# old_main_board.net
KiCad netlist of a schematic drawn in EAGLE
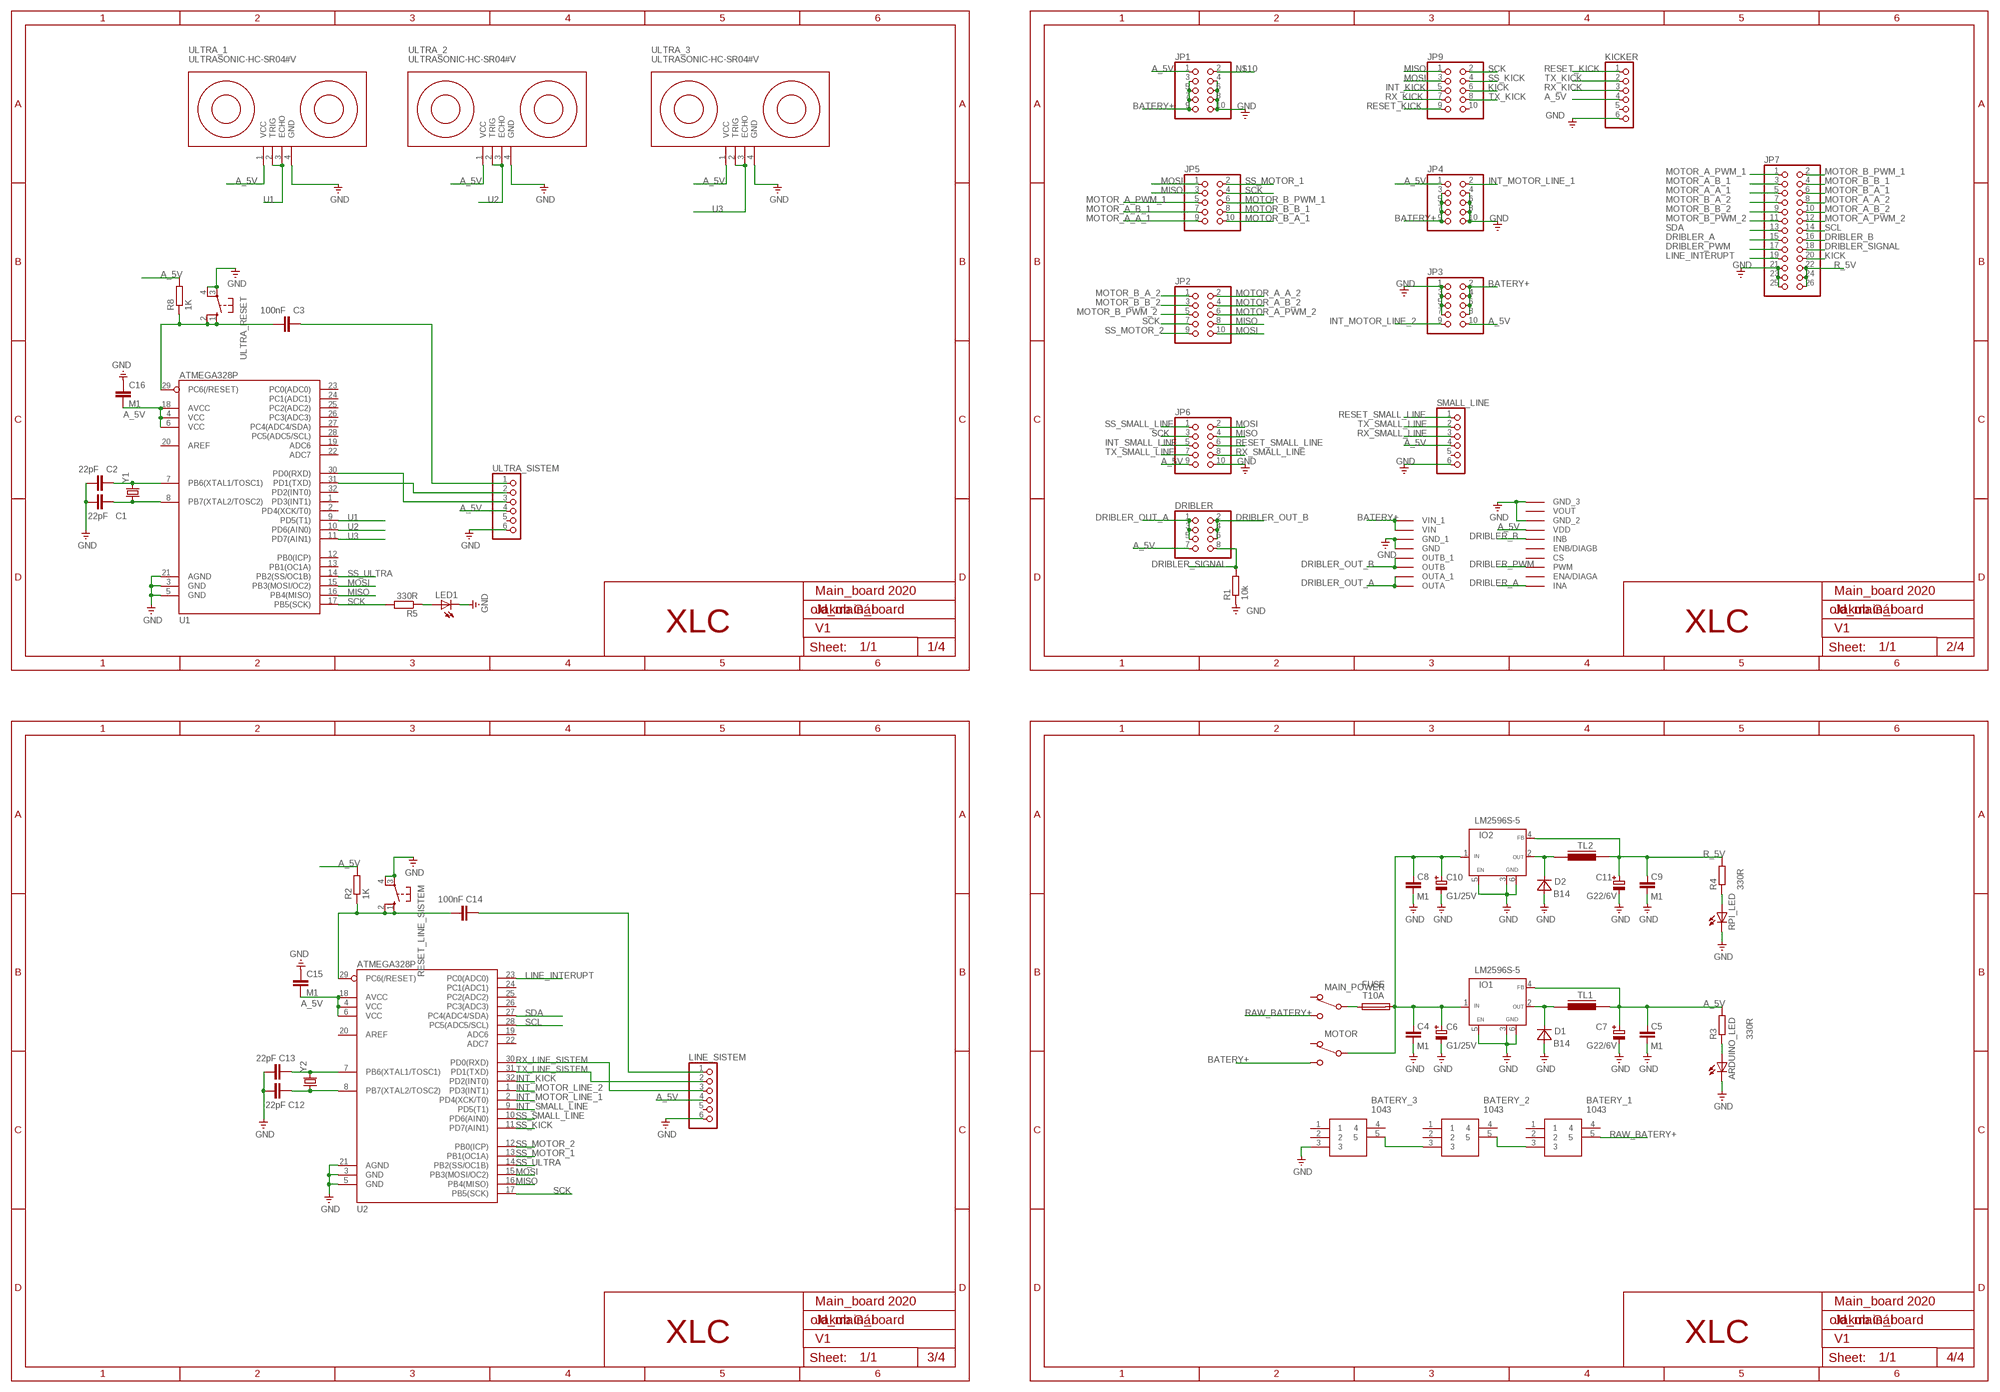
[diagram p0: schematic, sheet 1]

(export (version "E")
  (design (tool "Eeschema 10.0.6"))
  (components
    (comp (ref "ARDUINO_LED")
      (value "LEDCHIPLED_0603")
      (footprint "eagle-import:CHIPLED_0603")
      (libsource (lib "eagle-import") (part "LEDCHIPLED_0603"))
    )
    (comp (ref "BATERY_1")
      (value "1043")
      (footprint "eagle-import:1043")
      (fields (field (name "MOUSER_PART_NUMBER") "534-1043"))
      (libsource (lib "eagle-import") (part "1043"))
    )
    (comp (ref "BATERY_2")
      (value "1043")
      (footprint "eagle-import:1043")
      (fields (field (name "MOUSER_PART_NUMBER") "534-1043"))
      (libsource (lib "eagle-import") (part "1043"))
    )
    (comp (ref "BATERY_3")
      (value "1043")
      (footprint "eagle-import:1043")
      (fields (field (name "MOUSER_PART_NUMBER") "534-1043"))
      (libsource (lib "eagle-import") (part "1043"))
    )
    (comp (ref "C1")
      (value "22pF")
      (footprint "eagle-import:C0603")
      (libsource (lib "eagle-import") (part "rcl@1_C-EUC0603"))
    )
    (comp (ref "C2")
      (value "22pF")
      (footprint "eagle-import:C0603")
      (libsource (lib "eagle-import") (part "rcl@1_C-EUC0603"))
    )
    (comp (ref "C3")
      (value "100nF")
      (footprint "eagle-import:C0603")
      (libsource (lib "eagle-import") (part "rcl@1_C-EUC0603"))
    )
    (comp (ref "C4")
      (value "M1")
      (footprint "eagle-import:SMD-1206")
      (libsource (lib "eagle-import") (part "KOND-KERAM1206-SMD"))
    )
    (comp (ref "C5")
      (value "M1")
      (footprint "eagle-import:SMD-1206")
      (libsource (lib "eagle-import") (part "KOND-KERAM1206-SMD"))
    )
    (comp (ref "C6")
      (value "G1/25V")
      (footprint "eagle-import:SMD-ELE-D")
      (libsource (lib "eagle-import") (part "KOND-ELEKTD-SMD"))
    )
    (comp (ref "C7")
      (value "G22/6V")
      (footprint "eagle-import:SMD-ELE-D")
      (libsource (lib "eagle-import") (part "KOND-ELEKTD-SMD"))
    )
    (comp (ref "C8")
      (value "M1")
      (footprint "eagle-import:SMD-1206")
      (libsource (lib "eagle-import") (part "KOND-KERAM1206-SMD"))
    )
    (comp (ref "C9")
      (value "M1")
      (footprint "eagle-import:SMD-1206")
      (libsource (lib "eagle-import") (part "KOND-KERAM1206-SMD"))
    )
    (comp (ref "C10")
      (value "G1/25V")
      (footprint "eagle-import:SMD-ELE-D")
      (libsource (lib "eagle-import") (part "KOND-ELEKTD-SMD"))
    )
    (comp (ref "C11")
      (value "G22/6V")
      (footprint "eagle-import:SMD-ELE-D")
      (libsource (lib "eagle-import") (part "KOND-ELEKTD-SMD"))
    )
    (comp (ref "C12")
      (value "22pF")
      (footprint "eagle-import:C0603")
      (libsource (lib "eagle-import") (part "rcl@1_C-EUC0603"))
    )
    (comp (ref "C13")
      (value "22pF")
      (footprint "eagle-import:C0603")
      (libsource (lib "eagle-import") (part "rcl@1_C-EUC0603"))
    )
    (comp (ref "C14")
      (value "100nF")
      (footprint "eagle-import:C0603")
      (libsource (lib "eagle-import") (part "rcl@1_C-EUC0603"))
    )
    (comp (ref "C15")
      (value "M1")
      (footprint "eagle-import:C0603")
      (libsource (lib "eagle-import") (part "C-EUC0603"))
    )
    (comp (ref "C16")
      (value "M1")
      (footprint "eagle-import:C0603")
      (libsource (lib "eagle-import") (part "C-EUC0603"))
    )
    (comp (ref "D1")
      (value "B14")
      (footprint "eagle-import:D-3,6X5,5")
      (libsource (lib "eagle-import") (part "DIODASMD-3,6X5,5"))
    )
    (comp (ref "D2")
      (value "B14")
      (footprint "eagle-import:D-3,6X5,5")
      (libsource (lib "eagle-import") (part "DIODASMD-3,6X5,5"))
    )
    (comp (ref "DRIBLER")
      (value "PINHD-2X4_2.54-SMD")
      (footprint "eagle-import:2X04SMD")
      (libsource (lib "eagle-import") (part "PINHD-2X4_2.54-SMD"))
    )
    (comp (ref "FUSE")
      (value "T10A")
      (footprint "eagle-import:SH22,5A")
      (libsource (lib "eagle-import") (part "POISTKA2A"))
    )
    (comp (ref "IO1")
      (value "LM2596S-5")
      (footprint "eagle-import:TO263-5")
      (libsource (lib "eagle-import") (part "LM2596S"))
    )
    (comp (ref "IO2")
      (value "LM2596S-5")
      (footprint "eagle-import:TO263-5")
      (libsource (lib "eagle-import") (part "LM2596S"))
    )
    (comp (ref "JP1")
      (value "PINHD-2X5IDC")
      (footprint "eagle-import:2X05_IDC")
      (libsource (lib "eagle-import") (part "PINHD-2X5IDC"))
    )
    (comp (ref "JP2")
      (value "PINHD-2X5IDC")
      (footprint "eagle-import:2X05_IDC")
      (libsource (lib "eagle-import") (part "PINHD-2X5IDC"))
    )
    (comp (ref "JP3")
      (value "PINHD-2X5IDC")
      (footprint "eagle-import:2X05_IDC")
      (libsource (lib "eagle-import") (part "PINHD-2X5IDC"))
    )
    (comp (ref "JP4")
      (value "PINHD-2X5IDC")
      (footprint "eagle-import:2X05_IDC")
      (libsource (lib "eagle-import") (part "PINHD-2X5IDC"))
    )
    (comp (ref "JP5")
      (value "PINHD-2X5IDC")
      (footprint "eagle-import:2X05_IDC")
      (libsource (lib "eagle-import") (part "PINHD-2X5IDC"))
    )
    (comp (ref "JP6")
      (value "PINHD-2X5IDC")
      (footprint "eagle-import:2X05_IDC")
      (libsource (lib "eagle-import") (part "PINHD-2X5IDC"))
    )
    (comp (ref "JP7")
      (value "PINHD-2X13_2.54")
      (footprint "eagle-import:2X13")
      (libsource (lib "eagle-import") (part "PINHD-2X13_2.54"))
    )
    (comp (ref "JP9")
      (value "PINHD-2X5IDC")
      (footprint "eagle-import:2X05_IDC")
      (libsource (lib "eagle-import") (part "PINHD-2X5IDC"))
    )
    (comp (ref "KICKER")
      (value "PINHD-1X6")
      (footprint "eagle-import:1X06")
      (libsource (lib "eagle-import") (part "PINHD-1X6"))
    )
    (comp (ref "LED1")
      (value "LEDCHIPLED_0603")
      (footprint "eagle-import:CHIPLED_0603")
      (libsource (lib "eagle-import") (part "LEDCHIPLED_0603"))
    )
    (comp (ref "LINE_SISTEM")
      (value "PINHD-1X6")
      (footprint "eagle-import:1X06")
      (libsource (lib "eagle-import") (part "PINHD-1X6"))
    )
    (comp (ref "MAIN_POWER")
      (value "PREP-1PB")
      (footprint "eagle-import:P-B069B")
      (libsource (lib "eagle-import") (part "PREP-1PB"))
    )
    (comp (ref "MOTOR")
      (value "PREP-1PB")
      (footprint "eagle-import:P-B069B")
      (libsource (lib "eagle-import") (part "PREP-1PB"))
    )
    (comp (ref "R1")
      (value "10k")
      (footprint "eagle-import:R0603")
      (libsource (lib "eagle-import") (part "R-EU_R0603"))
    )
    (comp (ref "R2")
      (value "1K")
      (footprint "eagle-import:R0603")
      (libsource (lib "eagle-import") (part "R-EU_R0603"))
    )
    (comp (ref "R3")
      (value "330R")
      (footprint "eagle-import:R0603")
      (libsource (lib "eagle-import") (part "R-EU_R0603"))
    )
    (comp (ref "R4")
      (value "330R")
      (footprint "eagle-import:R0603")
      (libsource (lib "eagle-import") (part "R-EU_R0603"))
    )
    (comp (ref "R5")
      (value "330R")
      (footprint "eagle-import:R0603")
      (libsource (lib "eagle-import") (part "R-EU_R0603"))
    )
    (comp (ref "R8")
      (value "1K")
      (footprint "eagle-import:R0603")
      (libsource (lib "eagle-import") (part "R-EU_R0603"))
    )
    (comp (ref "RESET_LINE_SISTEM")
      (value "10-XX")
      (footprint "eagle-import:B3F-10XX")
      (fields (field (name "MPN") "B3F-1000"))
      (libsource (lib "eagle-import") (part "10-XX"))
    )
    (comp (ref "RPI_LED")
      (value "LEDCHIPLED_0603")
      (footprint "eagle-import:CHIPLED_0603")
      (libsource (lib "eagle-import") (part "LEDCHIPLED_0603"))
    )
    (comp (ref "SMALL_LINE")
      (value "PINHD-1X6")
      (footprint "eagle-import:1X06")
      (libsource (lib "eagle-import") (part "PINHD-1X6"))
    )
    (comp (ref "TL1")
      (value "INDUK-TLSMD1")
      (footprint "eagle-import:INDUK-TL")
      (libsource (lib "eagle-import") (part "INDUK-TLSMD1"))
    )
    (comp (ref "TL2")
      (value "INDUK-TLSMD1")
      (footprint "eagle-import:INDUK-TL")
      (libsource (lib "eagle-import") (part "INDUK-TLSMD1"))
    )
    (comp (ref "U$4")
      (value "MOTOR_DRIVER")
      (footprint "eagle-import:MOTOR_DRIVER")
      (libsource (lib "eagle-import") (part "MOTOR_DRIVER"))
    )
    (comp (ref "U1")
      (value "ATMEGA328P")
      (footprint "eagle-import:TQFP32-08")
      (libsource (lib "eagle-import") (part "ATMEGA328_SMT"))
    )
    (comp (ref "U2")
      (value "ATMEGA328P")
      (footprint "eagle-import:TQFP32-08")
      (libsource (lib "eagle-import") (part "ATMEGA328_SMT"))
    )
    (comp (ref "ULTRA_1")
      (value "ULTRASONIC-HC-SR04#V")
      (footprint "eagle-import:ULTRASONIC-HC-SR04#V")
      (libsource (lib "eagle-import") (part "ULTRASONIC-HC-SR04#V"))
    )
    (comp (ref "ULTRA_2")
      (value "ULTRASONIC-HC-SR04#V")
      (footprint "eagle-import:ULTRASONIC-HC-SR04#V")
      (libsource (lib "eagle-import") (part "ULTRASONIC-HC-SR04#V"))
    )
    (comp (ref "ULTRA_3")
      (value "ULTRASONIC-HC-SR04#V")
      (footprint "eagle-import:ULTRASONIC-HC-SR04#V")
      (libsource (lib "eagle-import") (part "ULTRASONIC-HC-SR04#V"))
    )
    (comp (ref "ULTRA_RESET")
      (value "10-XX")
      (footprint "eagle-import:B3F-10XX")
      (fields (field (name "MPN") "B3F-1000"))
      (libsource (lib "eagle-import") (part "10-XX"))
    )
    (comp (ref "ULTRA_SISTEM")
      (value "PINHD-1X6")
      (footprint "eagle-import:1X06")
      (libsource (lib "eagle-import") (part "PINHD-1X6"))
    )
    (comp (ref "Y1")
      (value "CRYSTALHC49US")
      (footprint "eagle-import:HC49US")
      (libsource (lib "eagle-import") (part "CRYSTALHC49US"))
    )
    (comp (ref "Y2")
      (value "CRYSTALHC49US")
      (footprint "eagle-import:HC49US")
      (libsource (lib "eagle-import") (part "CRYSTALHC49US"))
    )
  )
  (nets
    (net (code "1") (name "/A_5V") (class "Default")
      (node (ref "C15") (pin "2") (pinfunction "2_2") (pintype "passive"))
      (node (ref "C16") (pin "2") (pinfunction "2_2") (pintype "passive"))
      (node (ref "C5") (pin "2") (pinfunction "2_2") (pintype "passive"))
      (node (ref "C7") (pin "PLUS") (pinfunction "PLUS_PLUS") (pintype "passive"))
      (node (ref "DRIBLER") (pin "7") (pinfunction "7_7") (pintype "passive"))
      (node (ref "IO1") (pin "4") (pinfunction "FB_4") (pintype "input"))
      (node (ref "JP1") (pin "1") (pinfunction "1_1") (pintype "passive"))
      (node (ref "JP3") (pin "10") (pinfunction "10_10") (pintype "passive"))
      (node (ref "JP4") (pin "1") (pinfunction "1_1") (pintype "passive"))
      (node (ref "JP6") (pin "9") (pinfunction "9_9") (pintype "passive"))
      (node (ref "KICKER") (pin "4") (pinfunction "4_4") (pintype "passive"))
      (node (ref "LINE_SISTEM") (pin "4") (pinfunction "4_4") (pintype "passive"))
      (node (ref "R2") (pin "2") (pinfunction "2_2") (pintype "passive"))
      (node (ref "R3") (pin "2") (pinfunction "2_2") (pintype "passive"))
      (node (ref "R8") (pin "2") (pinfunction "2_2") (pintype "passive"))
      (node (ref "SMALL_LINE") (pin "4") (pinfunction "4_4") (pintype "passive"))
      (node (ref "TL1") (pin "2") (pinfunction "2_2") (pintype "passive"))
      (node (ref "U$4") (pin "VDD") (pinfunction "VDD_VDD") (pintype "bidirectional"))
      (node (ref "U1") (pin "18") (pinfunction "AVCC_18") (pintype "bidirectional"))
      (node (ref "U1") (pin "4") (pinfunction "VCC_4") (pintype "bidirectional"))
      (node (ref "U1") (pin "6") (pinfunction "VCC_6") (pintype "bidirectional"))
      (node (ref "U2") (pin "18") (pinfunction "AVCC_18") (pintype "bidirectional"))
      (node (ref "U2") (pin "4") (pinfunction "VCC_4") (pintype "bidirectional"))
      (node (ref "U2") (pin "6") (pinfunction "VCC_6") (pintype "bidirectional"))
      (node (ref "ULTRA_1") (pin "1") (pinfunction "VCC_1") (pintype "power_in"))
      (node (ref "ULTRA_2") (pin "1") (pinfunction "VCC_1") (pintype "power_in"))
      (node (ref "ULTRA_3") (pin "1") (pinfunction "VCC_1") (pintype "power_in"))
      (node (ref "ULTRA_SISTEM") (pin "4") (pinfunction "4_4") (pintype "passive"))
    )
    (net (code "2") (name "/BATERY+") (class "Default")
      (node (ref "JP1") (pin "3") (pinfunction "3_3") (pintype "passive"))
      (node (ref "JP1") (pin "5") (pinfunction "5_5") (pintype "passive"))
      (node (ref "JP1") (pin "7") (pinfunction "7_7") (pintype "passive"))
      (node (ref "JP1") (pin "9") (pinfunction "9_9") (pintype "passive"))
      (node (ref "JP3") (pin "2") (pinfunction "2_2") (pintype "passive"))
      (node (ref "JP3") (pin "4") (pinfunction "4_4") (pintype "passive"))
      (node (ref "JP3") (pin "6") (pinfunction "6_6") (pintype "passive"))
      (node (ref "JP3") (pin "8") (pinfunction "8_8") (pintype "passive"))
      (node (ref "JP4") (pin "3") (pinfunction "3_3") (pintype "passive"))
      (node (ref "JP4") (pin "5") (pinfunction "5_5") (pintype "passive"))
      (node (ref "JP4") (pin "7") (pinfunction "7_7") (pintype "passive"))
      (node (ref "JP4") (pin "9") (pinfunction "9_9") (pintype "passive"))
      (node (ref "MOTOR") (pin "1") (pinfunction "1-OFF_1") (pintype "passive"))
      (node (ref "U$4") (pin "VIN") (pinfunction "VIN_VIN") (pintype "bidirectional"))
      (node (ref "U$4") (pin "VIN_1") (pinfunction "VIN_1_VIN_1") (pintype "bidirectional"))
    )
    (net (code "3") (name "/DRIBLER_A") (class "Default")
      (node (ref "JP7") (pin "15") (pinfunction "15_15") (pintype "passive"))
      (node (ref "U$4") (pin "INA") (pinfunction "INA_INA") (pintype "bidirectional"))
    )
    (net (code "4") (name "/DRIBLER_B") (class "Default")
      (node (ref "JP7") (pin "16") (pinfunction "16_16") (pintype "passive"))
      (node (ref "U$4") (pin "INB") (pinfunction "INB_INB") (pintype "bidirectional"))
    )
    (net (code "5") (name "/DRIBLER_OUT_A") (class "Default")
      (node (ref "DRIBLER") (pin "1") (pinfunction "1_1") (pintype "passive"))
      (node (ref "DRIBLER") (pin "3") (pinfunction "3_3") (pintype "passive"))
      (node (ref "DRIBLER") (pin "5") (pinfunction "5_5") (pintype "passive"))
      (node (ref "U$4") (pin "OUTA") (pinfunction "OUTA_OUTA") (pintype "bidirectional"))
      (node (ref "U$4") (pin "OUTA_1") (pinfunction "OUTA_1_OUTA_1") (pintype "bidirectional"))
    )
    (net (code "6") (name "/DRIBLER_OUT_B") (class "Default")
      (node (ref "DRIBLER") (pin "2") (pinfunction "2_2") (pintype "passive"))
      (node (ref "DRIBLER") (pin "4") (pinfunction "4_4") (pintype "passive"))
      (node (ref "DRIBLER") (pin "6") (pinfunction "6_6") (pintype "passive"))
      (node (ref "U$4") (pin "OUTB") (pinfunction "OUTB_OUTB") (pintype "bidirectional"))
      (node (ref "U$4") (pin "OUTB_1") (pinfunction "OUTB_1_OUTB_1") (pintype "bidirectional"))
    )
    (net (code "7") (name "/DRIBLER_PWM") (class "Default")
      (node (ref "JP7") (pin "17") (pinfunction "17_17") (pintype "passive"))
      (node (ref "U$4") (pin "PWM") (pinfunction "PWM_PWM") (pintype "bidirectional"))
    )
    (net (code "8") (name "/DRIBLER_SIGNAL") (class "Default")
      (node (ref "DRIBLER") (pin "8") (pinfunction "8_8") (pintype "passive"))
      (node (ref "JP7") (pin "18") (pinfunction "18_18") (pintype "passive"))
      (node (ref "R1") (pin "2") (pinfunction "2_2") (pintype "passive"))
    )
    (net (code "9") (name "/INT_KICK") (class "Default")
      (node (ref "JP9") (pin "5") (pinfunction "5_5") (pintype "passive"))
      (node (ref "U2") (pin "32") (pinfunction "PD2(INT0)_32") (pintype "bidirectional"))
    )
    (net (code "10") (name "/INT_MOTOR_LINE_1") (class "Default")
      (node (ref "JP4") (pin "2") (pinfunction "2_2") (pintype "passive"))
      (node (ref "U2") (pin "2") (pinfunction "PD4(XCK/T0)_2") (pintype "bidirectional"))
    )
    (net (code "11") (name "/INT_MOTOR_LINE_2") (class "Default")
      (node (ref "JP3") (pin "9") (pinfunction "9_9") (pintype "passive"))
      (node (ref "U2") (pin "1") (pinfunction "PD3(INT1)_1") (pintype "bidirectional"))
    )
    (net (code "12") (name "/INT_SMALL_LINE") (class "Default")
      (node (ref "JP6") (pin "5") (pinfunction "5_5") (pintype "passive"))
      (node (ref "U2") (pin "9") (pinfunction "PD5(T1)_9") (pintype "bidirectional"))
    )
    (net (code "13") (name "/KICK") (class "Default")
      (node (ref "JP7") (pin "20") (pinfunction "20_20") (pintype "passive"))
      (node (ref "JP9") (pin "6") (pinfunction "6_6") (pintype "passive"))
    )
    (net (code "14") (name "/LINE_INTERUPT") (class "Default")
      (node (ref "JP7") (pin "19") (pinfunction "19_19") (pintype "passive"))
      (node (ref "U2") (pin "23") (pinfunction "PC0(ADC0)_23") (pintype "bidirectional"))
    )
    (net (code "15") (name "/MISO") (class "Default")
      (node (ref "JP2") (pin "8") (pinfunction "8_8") (pintype "passive"))
      (node (ref "JP5") (pin "3") (pinfunction "3_3") (pintype "passive"))
      (node (ref "JP6") (pin "4") (pinfunction "4_4") (pintype "passive"))
      (node (ref "JP9") (pin "1") (pinfunction "1_1") (pintype "passive"))
      (node (ref "U1") (pin "16") (pinfunction "PB4(MISO)_16") (pintype "bidirectional"))
      (node (ref "U2") (pin "16") (pinfunction "PB4(MISO)_16") (pintype "bidirectional"))
    )
    (net (code "16") (name "/MOSI") (class "Default")
      (node (ref "JP2") (pin "10") (pinfunction "10_10") (pintype "passive"))
      (node (ref "JP5") (pin "1") (pinfunction "1_1") (pintype "passive"))
      (node (ref "JP6") (pin "2") (pinfunction "2_2") (pintype "passive"))
      (node (ref "JP9") (pin "3") (pinfunction "3_3") (pintype "passive"))
      (node (ref "U1") (pin "15") (pinfunction "PB3(MOSI/OC2)_15") (pintype "bidirectional"))
      (node (ref "U2") (pin "15") (pinfunction "PB3(MOSI/OC2)_15") (pintype "bidirectional"))
    )
    (net (code "17") (name "/MOTOR_A_A_1") (class "Default")
      (node (ref "JP5") (pin "9") (pinfunction "9_9") (pintype "passive"))
      (node (ref "JP7") (pin "5") (pinfunction "5_5") (pintype "passive"))
    )
    (net (code "18") (name "/MOTOR_A_A_2") (class "Default")
      (node (ref "JP2") (pin "2") (pinfunction "2_2") (pintype "passive"))
      (node (ref "JP7") (pin "8") (pinfunction "8_8") (pintype "passive"))
    )
    (net (code "19") (name "/MOTOR_A_B_1") (class "Default")
      (node (ref "JP5") (pin "7") (pinfunction "7_7") (pintype "passive"))
      (node (ref "JP7") (pin "3") (pinfunction "3_3") (pintype "passive"))
    )
    (net (code "20") (name "/MOTOR_A_B_2") (class "Default")
      (node (ref "JP2") (pin "4") (pinfunction "4_4") (pintype "passive"))
      (node (ref "JP7") (pin "10") (pinfunction "10_10") (pintype "passive"))
    )
    (net (code "21") (name "/MOTOR_A_PWM_1") (class "Default")
      (node (ref "JP5") (pin "5") (pinfunction "5_5") (pintype "passive"))
      (node (ref "JP7") (pin "1") (pinfunction "1_1") (pintype "passive"))
    )
    (net (code "22") (name "/MOTOR_A_PWM_2") (class "Default")
      (node (ref "JP2") (pin "6") (pinfunction "6_6") (pintype "passive"))
      (node (ref "JP7") (pin "12") (pinfunction "12_12") (pintype "passive"))
    )
    (net (code "23") (name "/MOTOR_B_A_1") (class "Default")
      (node (ref "JP5") (pin "10") (pinfunction "10_10") (pintype "passive"))
      (node (ref "JP7") (pin "6") (pinfunction "6_6") (pintype "passive"))
    )
    (net (code "24") (name "/MOTOR_B_A_2") (class "Default")
      (node (ref "JP2") (pin "1") (pinfunction "1_1") (pintype "passive"))
      (node (ref "JP7") (pin "7") (pinfunction "7_7") (pintype "passive"))
    )
    (net (code "25") (name "/MOTOR_B_B_1") (class "Default")
      (node (ref "JP5") (pin "8") (pinfunction "8_8") (pintype "passive"))
      (node (ref "JP7") (pin "4") (pinfunction "4_4") (pintype "passive"))
    )
    (net (code "26") (name "/MOTOR_B_B_2") (class "Default")
      (node (ref "JP2") (pin "3") (pinfunction "3_3") (pintype "passive"))
      (node (ref "JP7") (pin "9") (pinfunction "9_9") (pintype "passive"))
    )
    (net (code "27") (name "/MOTOR_B_PWM_1") (class "Default")
      (node (ref "JP5") (pin "6") (pinfunction "6_6") (pintype "passive"))
      (node (ref "JP7") (pin "2") (pinfunction "2_2") (pintype "passive"))
    )
    (net (code "28") (name "/MOTOR_B_PWM_2") (class "Default")
      (node (ref "JP2") (pin "5") (pinfunction "5_5") (pintype "passive"))
      (node (ref "JP7") (pin "11") (pinfunction "11_11") (pintype "passive"))
    )
    (net (code "29") (name "/N$10") (class "Default")
      (node (ref "JP1") (pin "2") (pinfunction "2_2") (pintype "passive"))
    )
    (net (code "30") (name "/RAW_BATERY+") (class "Default")
      (node (ref "BATERY_1") (pin "5") (pinfunction "5_5") (pintype "bidirectional"))
      (node (ref "MAIN_POWER") (pin "1") (pinfunction "1-OFF_1") (pintype "passive"))
    )
    (net (code "31") (name "/RESET_KICK") (class "Default")
      (node (ref "JP9") (pin "9") (pinfunction "9_9") (pintype "passive"))
      (node (ref "KICKER") (pin "1") (pinfunction "1_1") (pintype "passive"))
    )
    (net (code "32") (name "/RESET_SMALL_LINE") (class "Default")
      (node (ref "JP6") (pin "6") (pinfunction "6_6") (pintype "passive"))
      (node (ref "SMALL_LINE") (pin "1") (pinfunction "1_1") (pintype "passive"))
    )
    (net (code "33") (name "/RX_KICK") (class "Default")
      (node (ref "JP9") (pin "7") (pinfunction "7_7") (pintype "passive"))
      (node (ref "KICKER") (pin "3") (pinfunction "3_3") (pintype "passive"))
    )
    (net (code "34") (name "/RX_LINE_SISTEM") (class "Default")
      (node (ref "LINE_SISTEM") (pin "3") (pinfunction "3_3") (pintype "passive"))
      (node (ref "U2") (pin "30") (pinfunction "PD0(RXD)_30") (pintype "bidirectional"))
    )
    (net (code "35") (name "/RX_SMALL_LINE") (class "Default")
      (node (ref "JP6") (pin "8") (pinfunction "8_8") (pintype "passive"))
      (node (ref "SMALL_LINE") (pin "3") (pinfunction "3_3") (pintype "passive"))
    )
    (net (code "36") (name "/R_5V") (class "Default")
      (node (ref "C11") (pin "PLUS") (pinfunction "PLUS_PLUS") (pintype "passive"))
      (node (ref "C9") (pin "2") (pinfunction "2_2") (pintype "passive"))
      (node (ref "IO2") (pin "4") (pinfunction "FB_4") (pintype "input"))
      (node (ref "JP7") (pin "22") (pinfunction "22_22") (pintype "passive"))
      (node (ref "JP7") (pin "24") (pinfunction "24_24") (pintype "passive"))
      (node (ref "JP7") (pin "26") (pinfunction "26_26") (pintype "passive"))
      (node (ref "R4") (pin "2") (pinfunction "2_2") (pintype "passive"))
      (node (ref "TL2") (pin "2") (pinfunction "2_2") (pintype "passive"))
    )
    (net (code "37") (name "/SCK") (class "Default")
      (node (ref "JP2") (pin "7") (pinfunction "7_7") (pintype "passive"))
      (node (ref "JP5") (pin "4") (pinfunction "4_4") (pintype "passive"))
      (node (ref "JP6") (pin "3") (pinfunction "3_3") (pintype "passive"))
      (node (ref "JP9") (pin "2") (pinfunction "2_2") (pintype "passive"))
      (node (ref "R5") (pin "2") (pinfunction "2_2") (pintype "passive"))
      (node (ref "U1") (pin "17") (pinfunction "PB5(SCK)_17") (pintype "bidirectional"))
      (node (ref "U2") (pin "17") (pinfunction "PB5(SCK)_17") (pintype "bidirectional"))
    )
    (net (code "38") (name "/SCL") (class "Default")
      (node (ref "JP7") (pin "14") (pinfunction "14_14") (pintype "passive"))
      (node (ref "U2") (pin "28") (pinfunction "PC5(ADC5/SCL)_28") (pintype "bidirectional"))
    )
    (net (code "39") (name "/SDA") (class "Default")
      (node (ref "JP7") (pin "13") (pinfunction "13_13") (pintype "passive"))
      (node (ref "U2") (pin "27") (pinfunction "PC4(ADC4/SDA)_27") (pintype "bidirectional"))
    )
    (net (code "40") (name "/SS_KICK") (class "Default")
      (node (ref "JP9") (pin "4") (pinfunction "4_4") (pintype "passive"))
      (node (ref "U2") (pin "11") (pinfunction "PD7(AIN1)_11") (pintype "bidirectional"))
    )
    (net (code "41") (name "/SS_MOTOR_1") (class "Default")
      (node (ref "JP5") (pin "2") (pinfunction "2_2") (pintype "passive"))
      (node (ref "U2") (pin "13") (pinfunction "PB1(OC1A)_13") (pintype "bidirectional"))
    )
    (net (code "42") (name "/SS_MOTOR_2") (class "Default")
      (node (ref "JP2") (pin "9") (pinfunction "9_9") (pintype "passive"))
      (node (ref "U2") (pin "12") (pinfunction "PB0(ICP)_12") (pintype "bidirectional"))
    )
    (net (code "43") (name "/SS_SMALL_LINE") (class "Default")
      (node (ref "JP6") (pin "1") (pinfunction "1_1") (pintype "passive"))
      (node (ref "U2") (pin "10") (pinfunction "PD6(AIN0)_10") (pintype "bidirectional"))
    )
    (net (code "44") (name "/SS_ULTRA") (class "Default")
      (node (ref "U1") (pin "14") (pinfunction "PB2(SS/OC1B)_14") (pintype "bidirectional"))
      (node (ref "U2") (pin "14") (pinfunction "PB2(SS/OC1B)_14") (pintype "bidirectional"))
    )
    (net (code "45") (name "/TX_KICK") (class "Default")
      (node (ref "JP9") (pin "8") (pinfunction "8_8") (pintype "passive"))
      (node (ref "KICKER") (pin "2") (pinfunction "2_2") (pintype "passive"))
    )
    (net (code "46") (name "/TX_LINE_SISTEM") (class "Default")
      (node (ref "LINE_SISTEM") (pin "2") (pinfunction "2_2") (pintype "passive"))
      (node (ref "U2") (pin "31") (pinfunction "PD1(TXD)_31") (pintype "bidirectional"))
    )
    (net (code "47") (name "/TX_SMALL_LINE") (class "Default")
      (node (ref "JP6") (pin "7") (pinfunction "7_7") (pintype "passive"))
      (node (ref "SMALL_LINE") (pin "2") (pinfunction "2_2") (pintype "passive"))
    )
    (net (code "48") (name "/U1") (class "Default")
      (node (ref "U1") (pin "9") (pinfunction "PD5(T1)_9") (pintype "bidirectional"))
      (node (ref "ULTRA_1") (pin "2") (pinfunction "TRIG_2") (pintype "input"))
      (node (ref "ULTRA_1") (pin "3") (pinfunction "ECHO_3") (pintype "output"))
    )
    (net (code "49") (name "/U2") (class "Default")
      (node (ref "U1") (pin "10") (pinfunction "PD6(AIN0)_10") (pintype "bidirectional"))
      (node (ref "ULTRA_2") (pin "2") (pinfunction "TRIG_2") (pintype "input"))
      (node (ref "ULTRA_2") (pin "3") (pinfunction "ECHO_3") (pintype "output"))
    )
    (net (code "50") (name "/U3") (class "Default")
      (node (ref "U1") (pin "11") (pinfunction "PD7(AIN1)_11") (pintype "bidirectional"))
      (node (ref "ULTRA_3") (pin "2") (pinfunction "TRIG_2") (pintype "input"))
      (node (ref "ULTRA_3") (pin "3") (pinfunction "ECHO_3") (pintype "output"))
    )
    (net (code "51") (name "GND") (class "Default")
      (node (ref "ARDUINO_LED") (pin "C") (pinfunction "C_C") (pintype "passive"))
      (node (ref "BATERY_3") (pin "3") (pinfunction "3_3") (pintype "bidirectional"))
      (node (ref "C1") (pin "1") (pinfunction "1_1") (pintype "passive"))
      (node (ref "C10") (pin "MINUS") (pinfunction "MINUS_MINUS") (pintype "passive"))
      (node (ref "C11") (pin "MINUS") (pinfunction "MINUS_MINUS") (pintype "passive"))
      (node (ref "C12") (pin "1") (pinfunction "1_1") (pintype "passive"))
      (node (ref "C13") (pin "1") (pinfunction "1_1") (pintype "passive"))
      (node (ref "C15") (pin "1") (pinfunction "1_1") (pintype "passive"))
      (node (ref "C16") (pin "1") (pinfunction "1_1") (pintype "passive"))
      (node (ref "C2") (pin "1") (pinfunction "1_1") (pintype "passive"))
      (node (ref "C4") (pin "1") (pinfunction "1_1") (pintype "passive"))
      (node (ref "C5") (pin "1") (pinfunction "1_1") (pintype "passive"))
      (node (ref "C6") (pin "MINUS") (pinfunction "MINUS_MINUS") (pintype "passive"))
      (node (ref "C7") (pin "MINUS") (pinfunction "MINUS_MINUS") (pintype "passive"))
      (node (ref "C8") (pin "1") (pinfunction "1_1") (pintype "passive"))
      (node (ref "C9") (pin "1") (pinfunction "1_1") (pintype "passive"))
      (node (ref "D1") (pin "A") (pinfunction "A_A") (pintype "passive"))
      (node (ref "D2") (pin "A") (pinfunction "A_A") (pintype "passive"))
      (node (ref "IO1") (pin "3") (pinfunction "GND_3") (pintype "power_in"))
      (node (ref "IO1") (pin "5") (pinfunction "EN_5") (pintype "input"))
      (node (ref "IO1") (pin "6") (pinfunction "GND_6") (pintype "power_in"))
      (node (ref "IO2") (pin "3") (pinfunction "GND_3") (pintype "power_in"))
      (node (ref "IO2") (pin "5") (pinfunction "EN_5") (pintype "input"))
      (node (ref "IO2") (pin "6") (pinfunction "GND_6") (pintype "power_in"))
      (node (ref "JP1") (pin "10") (pinfunction "10_10") (pintype "passive"))
      (node (ref "JP1") (pin "4") (pinfunction "4_4") (pintype "passive"))
      (node (ref "JP1") (pin "6") (pinfunction "6_6") (pintype "passive"))
      (node (ref "JP1") (pin "8") (pinfunction "8_8") (pintype "passive"))
      (node (ref "JP3") (pin "1") (pinfunction "1_1") (pintype "passive"))
      (node (ref "JP3") (pin "3") (pinfunction "3_3") (pintype "passive"))
      (node (ref "JP3") (pin "5") (pinfunction "5_5") (pintype "passive"))
      (node (ref "JP3") (pin "7") (pinfunction "7_7") (pintype "passive"))
      (node (ref "JP4") (pin "10") (pinfunction "10_10") (pintype "passive"))
      (node (ref "JP4") (pin "4") (pinfunction "4_4") (pintype "passive"))
      (node (ref "JP4") (pin "6") (pinfunction "6_6") (pintype "passive"))
      (node (ref "JP4") (pin "8") (pinfunction "8_8") (pintype "passive"))
      (node (ref "JP6") (pin "10") (pinfunction "10_10") (pintype "passive"))
      (node (ref "JP7") (pin "21") (pinfunction "21_21") (pintype "passive"))
      (node (ref "JP7") (pin "23") (pinfunction "23_23") (pintype "passive"))
      (node (ref "JP7") (pin "25") (pinfunction "25_25") (pintype "passive"))
      (node (ref "KICKER") (pin "6") (pinfunction "6_6") (pintype "passive"))
      (node (ref "LED1") (pin "C") (pinfunction "C_C") (pintype "passive"))
      (node (ref "LINE_SISTEM") (pin "6") (pinfunction "6_6") (pintype "passive"))
      (node (ref "R1") (pin "1") (pinfunction "1_1") (pintype "passive"))
      (node (ref "RESET_LINE_SISTEM") (pin "3") (pinfunction "P_3") (pintype "passive"))
      (node (ref "RESET_LINE_SISTEM") (pin "4") (pinfunction "P1_4") (pintype "passive"))
      (node (ref "RPI_LED") (pin "C") (pinfunction "C_C") (pintype "passive"))
      (node (ref "SMALL_LINE") (pin "6") (pinfunction "6_6") (pintype "passive"))
      (node (ref "U$4") (pin "GND") (pinfunction "GND_GND") (pintype "bidirectional"))
      (node (ref "U$4") (pin "GND_1") (pinfunction "GND_1_GND_1") (pintype "bidirectional"))
      (node (ref "U$4") (pin "GND_2") (pinfunction "GND_2_GND_2") (pintype "bidirectional"))
      (node (ref "U$4") (pin "GND_3") (pinfunction "GND_3_GND_3") (pintype "bidirectional"))
      (node (ref "U1") (pin "21") (pinfunction "AGND_21") (pintype "bidirectional"))
      (node (ref "U1") (pin "3") (pinfunction "GND_3") (pintype "bidirectional"))
      (node (ref "U1") (pin "5") (pinfunction "GND_5") (pintype "bidirectional"))
      (node (ref "U2") (pin "21") (pinfunction "AGND_21") (pintype "bidirectional"))
      (node (ref "U2") (pin "3") (pinfunction "GND_3") (pintype "bidirectional"))
      (node (ref "U2") (pin "5") (pinfunction "GND_5") (pintype "bidirectional"))
      (node (ref "ULTRA_1") (pin "4") (pinfunction "GND_4") (pintype "power_in"))
      (node (ref "ULTRA_2") (pin "4") (pinfunction "GND_4") (pintype "power_in"))
      (node (ref "ULTRA_3") (pin "4") (pinfunction "GND_4") (pintype "power_in"))
      (node (ref "ULTRA_RESET") (pin "3") (pinfunction "P_3") (pintype "passive"))
      (node (ref "ULTRA_RESET") (pin "4") (pinfunction "P1_4") (pintype "passive"))
      (node (ref "ULTRA_SISTEM") (pin "6") (pinfunction "6_6") (pintype "passive"))
    )
    (net (code "52") (name "Net-(ARDUINO_LED-PadA)") (class "Default")
      (node (ref "ARDUINO_LED") (pin "A") (pinfunction "A_A") (pintype "passive"))
      (node (ref "R3") (pin "1") (pinfunction "1_1") (pintype "passive"))
    )
    (net (code "53") (name "Net-(BATERY_1-Pad3)") (class "Default")
      (node (ref "BATERY_1") (pin "3") (pinfunction "3_3") (pintype "bidirectional"))
      (node (ref "BATERY_2") (pin "5") (pinfunction "5_5") (pintype "bidirectional"))
    )
    (net (code "54") (name "Net-(BATERY_2-Pad3)") (class "Default")
      (node (ref "BATERY_2") (pin "3") (pinfunction "3_3") (pintype "bidirectional"))
      (node (ref "BATERY_3") (pin "5") (pinfunction "5_5") (pintype "bidirectional"))
    )
    (net (code "55") (name "Net-(C3-Pad2)") (class "Default")
      (node (ref "C3") (pin "2") (pinfunction "2_2") (pintype "passive"))
      (node (ref "ULTRA_SISTEM") (pin "1") (pinfunction "1_1") (pintype "passive"))
    )
    (net (code "56") (name "Net-(C14-Pad2)") (class "Default")
      (node (ref "C14") (pin "2") (pinfunction "2_2") (pintype "passive"))
      (node (ref "LINE_SISTEM") (pin "1") (pinfunction "1_1") (pintype "passive"))
    )
    (net (code "57") (name "Net-(IO1-IN)") (class "Default")
      (node (ref "C10") (pin "PLUS") (pinfunction "PLUS_PLUS") (pintype "passive"))
      (node (ref "C4") (pin "2") (pinfunction "2_2") (pintype "passive"))
      (node (ref "C6") (pin "PLUS") (pinfunction "PLUS_PLUS") (pintype "passive"))
      (node (ref "C8") (pin "2") (pinfunction "2_2") (pintype "passive"))
      (node (ref "FUSE") (pin "2") (pinfunction "2_2") (pintype "passive"))
      (node (ref "IO1") (pin "1") (pinfunction "IN_1") (pintype "input"))
      (node (ref "IO2") (pin "1") (pinfunction "IN_1") (pintype "input"))
      (node (ref "MOTOR") (pin "2") (pinfunction "2-COM_2") (pintype "passive"))
    )
    (net (code "58") (name "Net-(IO1-OUT)") (class "Default")
      (node (ref "D1") (pin "K") (pinfunction "K_K") (pintype "passive"))
      (node (ref "IO1") (pin "2") (pinfunction "OUT_2") (pintype "output"))
      (node (ref "TL1") (pin "1") (pinfunction "1_1") (pintype "passive"))
    )
    (net (code "59") (name "Net-(IO2-OUT)") (class "Default")
      (node (ref "D2") (pin "K") (pinfunction "K_K") (pintype "passive"))
      (node (ref "IO2") (pin "2") (pinfunction "OUT_2") (pintype "output"))
      (node (ref "TL2") (pin "1") (pinfunction "1_1") (pintype "passive"))
    )
    (net (code "60") (name "Net-(LED1-PadA)") (class "Default")
      (node (ref "LED1") (pin "A") (pinfunction "A_A") (pintype "passive"))
      (node (ref "R5") (pin "1") (pinfunction "1_1") (pintype "passive"))
    )
    (net (code "61") (name "Net-(MAIN_POWER-2-COM)") (class "Default")
      (node (ref "FUSE") (pin "1") (pinfunction "1_1") (pintype "passive"))
      (node (ref "MAIN_POWER") (pin "2") (pinfunction "2-COM_2") (pintype "passive"))
    )
    (net (code "62") (name "Net-(R4-Pad1)") (class "Default")
      (node (ref "R4") (pin "1") (pinfunction "1_1") (pintype "passive"))
      (node (ref "RPI_LED") (pin "A") (pinfunction "A_A") (pintype "passive"))
    )
    (net (code "63") (name "Net-(RESET_LINE_SISTEM-S)") (class "Default")
      (node (ref "C14") (pin "1") (pinfunction "1_1") (pintype "passive"))
      (node (ref "R2") (pin "1") (pinfunction "1_1") (pintype "passive"))
      (node (ref "RESET_LINE_SISTEM") (pin "1") (pinfunction "S_1") (pintype "passive"))
      (node (ref "RESET_LINE_SISTEM") (pin "2") (pinfunction "S1_2") (pintype "passive"))
      (node (ref "U2") (pin "29") (pinfunction "PC6(/RESET)_29") (pintype "bidirectional"))
    )
    (net (code "64") (name "Net-(U1-PB6(XTAL1{slash}TOSC1))") (class "Default")
      (node (ref "C2") (pin "2") (pinfunction "2_2") (pintype "passive"))
      (node (ref "U1") (pin "7") (pinfunction "PB6(XTAL1/TOSC1)_7") (pintype "bidirectional"))
      (node (ref "Y1") (pin "2") (pinfunction "2_2") (pintype "passive"))
    )
    (net (code "65") (name "Net-(U1-PB7(XTAL2{slash}TOSC2))") (class "Default")
      (node (ref "C1") (pin "2") (pinfunction "2_2") (pintype "passive"))
      (node (ref "U1") (pin "8") (pinfunction "PB7(XTAL2/TOSC2)_8") (pintype "bidirectional"))
      (node (ref "Y1") (pin "1") (pinfunction "1_1") (pintype "passive"))
    )
    (net (code "66") (name "Net-(U1-PC6({slash}RESET))") (class "Default")
      (node (ref "C3") (pin "1") (pinfunction "1_1") (pintype "passive"))
      (node (ref "R8") (pin "1") (pinfunction "1_1") (pintype "passive"))
      (node (ref "U1") (pin "29") (pinfunction "PC6(/RESET)_29") (pintype "bidirectional"))
      (node (ref "ULTRA_RESET") (pin "1") (pinfunction "S_1") (pintype "passive"))
      (node (ref "ULTRA_RESET") (pin "2") (pinfunction "S1_2") (pintype "passive"))
    )
    (net (code "67") (name "Net-(U1-PD0(RXD))") (class "Default")
      (node (ref "U1") (pin "30") (pinfunction "PD0(RXD)_30") (pintype "bidirectional"))
      (node (ref "ULTRA_SISTEM") (pin "3") (pinfunction "3_3") (pintype "passive"))
    )
    (net (code "68") (name "Net-(U1-PD1(TXD))") (class "Default")
      (node (ref "U1") (pin "31") (pinfunction "PD1(TXD)_31") (pintype "bidirectional"))
      (node (ref "ULTRA_SISTEM") (pin "2") (pinfunction "2_2") (pintype "passive"))
    )
    (net (code "69") (name "Net-(U2-PB6(XTAL1{slash}TOSC1))") (class "Default")
      (node (ref "C13") (pin "2") (pinfunction "2_2") (pintype "passive"))
      (node (ref "U2") (pin "7") (pinfunction "PB6(XTAL1/TOSC1)_7") (pintype "bidirectional"))
      (node (ref "Y2") (pin "2") (pinfunction "2_2") (pintype "passive"))
    )
    (net (code "70") (name "Net-(U2-PB7(XTAL2{slash}TOSC2))") (class "Default")
      (node (ref "C12") (pin "2") (pinfunction "2_2") (pintype "passive"))
      (node (ref "U2") (pin "8") (pinfunction "PB7(XTAL2/TOSC2)_8") (pintype "bidirectional"))
      (node (ref "Y2") (pin "1") (pinfunction "1_1") (pintype "passive"))
    )
    (net (code "71") (name "unconnected-(BATERY_1-Pad1)") (class "Default")
      (node (ref "BATERY_1") (pin "1") (pinfunction "1_1") (pintype "bidirectional"))
    )
    (net (code "72") (name "unconnected-(BATERY_1-Pad2)") (class "Default")
      (node (ref "BATERY_1") (pin "2") (pinfunction "2_2") (pintype "bidirectional"))
    )
    (net (code "73") (name "unconnected-(BATERY_1-Pad4)") (class "Default")
      (node (ref "BATERY_1") (pin "4") (pinfunction "4_4") (pintype "bidirectional"))
    )
    (net (code "74") (name "unconnected-(BATERY_2-Pad1)") (class "Default")
      (node (ref "BATERY_2") (pin "1") (pinfunction "1_1") (pintype "bidirectional"))
    )
    (net (code "75") (name "unconnected-(BATERY_2-Pad2)") (class "Default")
      (node (ref "BATERY_2") (pin "2") (pinfunction "2_2") (pintype "bidirectional"))
    )
    (net (code "76") (name "unconnected-(BATERY_2-Pad4)") (class "Default")
      (node (ref "BATERY_2") (pin "4") (pinfunction "4_4") (pintype "bidirectional"))
    )
    (net (code "77") (name "unconnected-(BATERY_3-Pad1)") (class "Default")
      (node (ref "BATERY_3") (pin "1") (pinfunction "1_1") (pintype "bidirectional"))
    )
    (net (code "78") (name "unconnected-(BATERY_3-Pad2)") (class "Default")
      (node (ref "BATERY_3") (pin "2") (pinfunction "2_2") (pintype "bidirectional"))
    )
    (net (code "79") (name "unconnected-(BATERY_3-Pad4)") (class "Default")
      (node (ref "BATERY_3") (pin "4") (pinfunction "4_4") (pintype "bidirectional"))
    )
    (net (code "80") (name "unconnected-(JP9-Pad10)") (class "Default")
      (node (ref "JP9") (pin "10") (pinfunction "10_10") (pintype "passive"))
    )
    (net (code "81") (name "unconnected-(KICKER-Pad5)") (class "Default")
      (node (ref "KICKER") (pin "5") (pinfunction "5_5") (pintype "passive"))
    )
    (net (code "82") (name "unconnected-(LINE_SISTEM-Pad5)") (class "Default")
      (node (ref "LINE_SISTEM") (pin "5") (pinfunction "5_5") (pintype "passive"))
    )
    (net (code "83") (name "unconnected-(MAIN_POWER-3-ON-Pad3)") (class "Default")
      (node (ref "MAIN_POWER") (pin "3") (pinfunction "3-ON_3") (pintype "passive"))
    )
    (net (code "84") (name "unconnected-(MOTOR-3-ON-Pad3)") (class "Default")
      (node (ref "MOTOR") (pin "3") (pinfunction "3-ON_3") (pintype "passive"))
    )
    (net (code "85") (name "unconnected-(SMALL_LINE-Pad5)") (class "Default")
      (node (ref "SMALL_LINE") (pin "5") (pinfunction "5_5") (pintype "passive"))
    )
    (net (code "86") (name "unconnected-(U$4-PadCS)") (class "Default")
      (node (ref "U$4") (pin "CS") (pinfunction "CS_CS") (pintype "bidirectional"))
    )
    (net (code "87") (name "unconnected-(U$4-PadENA{slash}DIAGA)") (class "Default")
      (node (ref "U$4") (pin "ENA/DIAGA") (pinfunction "ENA/DIAGA_ENA/DIAGA") (pintype "bidirectional"))
    )
    (net (code "88") (name "unconnected-(U$4-PadENB{slash}DIAGB)") (class "Default")
      (node (ref "U$4") (pin "ENB/DIAGB") (pinfunction "ENB/DIAGB_ENB/DIAGB") (pintype "bidirectional"))
    )
    (net (code "89") (name "unconnected-(U$4-PadVOUT)") (class "Default")
      (node (ref "U$4") (pin "VOUT") (pinfunction "VOUT_VOUT") (pintype "bidirectional"))
    )
    (net (code "90") (name "unconnected-(U1-ADC6-Pad19)") (class "Default")
      (node (ref "U1") (pin "19") (pinfunction "ADC6_19") (pintype "bidirectional"))
    )
    (net (code "91") (name "unconnected-(U1-ADC7-Pad22)") (class "Default")
      (node (ref "U1") (pin "22") (pinfunction "ADC7_22") (pintype "bidirectional"))
    )
    (net (code "92") (name "unconnected-(U1-AREF-Pad20)") (class "Default")
      (node (ref "U1") (pin "20") (pinfunction "AREF_20") (pintype "bidirectional"))
    )
    (net (code "93") (name "unconnected-(U1-PB0(ICP)-Pad12)") (class "Default")
      (node (ref "U1") (pin "12") (pinfunction "PB0(ICP)_12") (pintype "bidirectional"))
    )
    (net (code "94") (name "unconnected-(U1-PB1(OC1A)-Pad13)") (class "Default")
      (node (ref "U1") (pin "13") (pinfunction "PB1(OC1A)_13") (pintype "bidirectional"))
    )
    (net (code "95") (name "unconnected-(U1-PC0(ADC0)-Pad23)") (class "Default")
      (node (ref "U1") (pin "23") (pinfunction "PC0(ADC0)_23") (pintype "bidirectional"))
    )
    (net (code "96") (name "unconnected-(U1-PC1(ADC1)-Pad24)") (class "Default")
      (node (ref "U1") (pin "24") (pinfunction "PC1(ADC1)_24") (pintype "bidirectional"))
    )
    (net (code "97") (name "unconnected-(U1-PC2(ADC2)-Pad25)") (class "Default")
      (node (ref "U1") (pin "25") (pinfunction "PC2(ADC2)_25") (pintype "bidirectional"))
    )
    (net (code "98") (name "unconnected-(U1-PC3(ADC3)-Pad26)") (class "Default")
      (node (ref "U1") (pin "26") (pinfunction "PC3(ADC3)_26") (pintype "bidirectional"))
    )
    (net (code "99") (name "unconnected-(U1-PC4(ADC4{slash}SDA)-Pad27)") (class "Default")
      (node (ref "U1") (pin "27") (pinfunction "PC4(ADC4/SDA)_27") (pintype "bidirectional"))
    )
    (net (code "100") (name "unconnected-(U1-PC5(ADC5{slash}SCL)-Pad28)") (class "Default")
      (node (ref "U1") (pin "28") (pinfunction "PC5(ADC5/SCL)_28") (pintype "bidirectional"))
    )
    (net (code "101") (name "unconnected-(U1-PD2(INT0)-Pad32)") (class "Default")
      (node (ref "U1") (pin "32") (pinfunction "PD2(INT0)_32") (pintype "bidirectional"))
    )
    (net (code "102") (name "unconnected-(U1-PD3(INT1)-Pad1)") (class "Default")
      (node (ref "U1") (pin "1") (pinfunction "PD3(INT1)_1") (pintype "bidirectional"))
    )
    (net (code "103") (name "unconnected-(U1-PD4(XCK{slash}T0)-Pad2)") (class "Default")
      (node (ref "U1") (pin "2") (pinfunction "PD4(XCK/T0)_2") (pintype "bidirectional"))
    )
    (net (code "104") (name "unconnected-(U2-ADC6-Pad19)") (class "Default")
      (node (ref "U2") (pin "19") (pinfunction "ADC6_19") (pintype "bidirectional"))
    )
    (net (code "105") (name "unconnected-(U2-ADC7-Pad22)") (class "Default")
      (node (ref "U2") (pin "22") (pinfunction "ADC7_22") (pintype "bidirectional"))
    )
    (net (code "106") (name "unconnected-(U2-AREF-Pad20)") (class "Default")
      (node (ref "U2") (pin "20") (pinfunction "AREF_20") (pintype "bidirectional"))
    )
    (net (code "107") (name "unconnected-(U2-PC1(ADC1)-Pad24)") (class "Default")
      (node (ref "U2") (pin "24") (pinfunction "PC1(ADC1)_24") (pintype "bidirectional"))
    )
    (net (code "108") (name "unconnected-(U2-PC2(ADC2)-Pad25)") (class "Default")
      (node (ref "U2") (pin "25") (pinfunction "PC2(ADC2)_25") (pintype "bidirectional"))
    )
    (net (code "109") (name "unconnected-(U2-PC3(ADC3)-Pad26)") (class "Default")
      (node (ref "U2") (pin "26") (pinfunction "PC3(ADC3)_26") (pintype "bidirectional"))
    )
    (net (code "110") (name "unconnected-(ULTRA_SISTEM-Pad5)") (class "Default")
      (node (ref "ULTRA_SISTEM") (pin "5") (pinfunction "5_5") (pintype "passive"))
    )
  )
)
